# ahrs.net
KiCad netlist of a schematic drawn in EAGLE
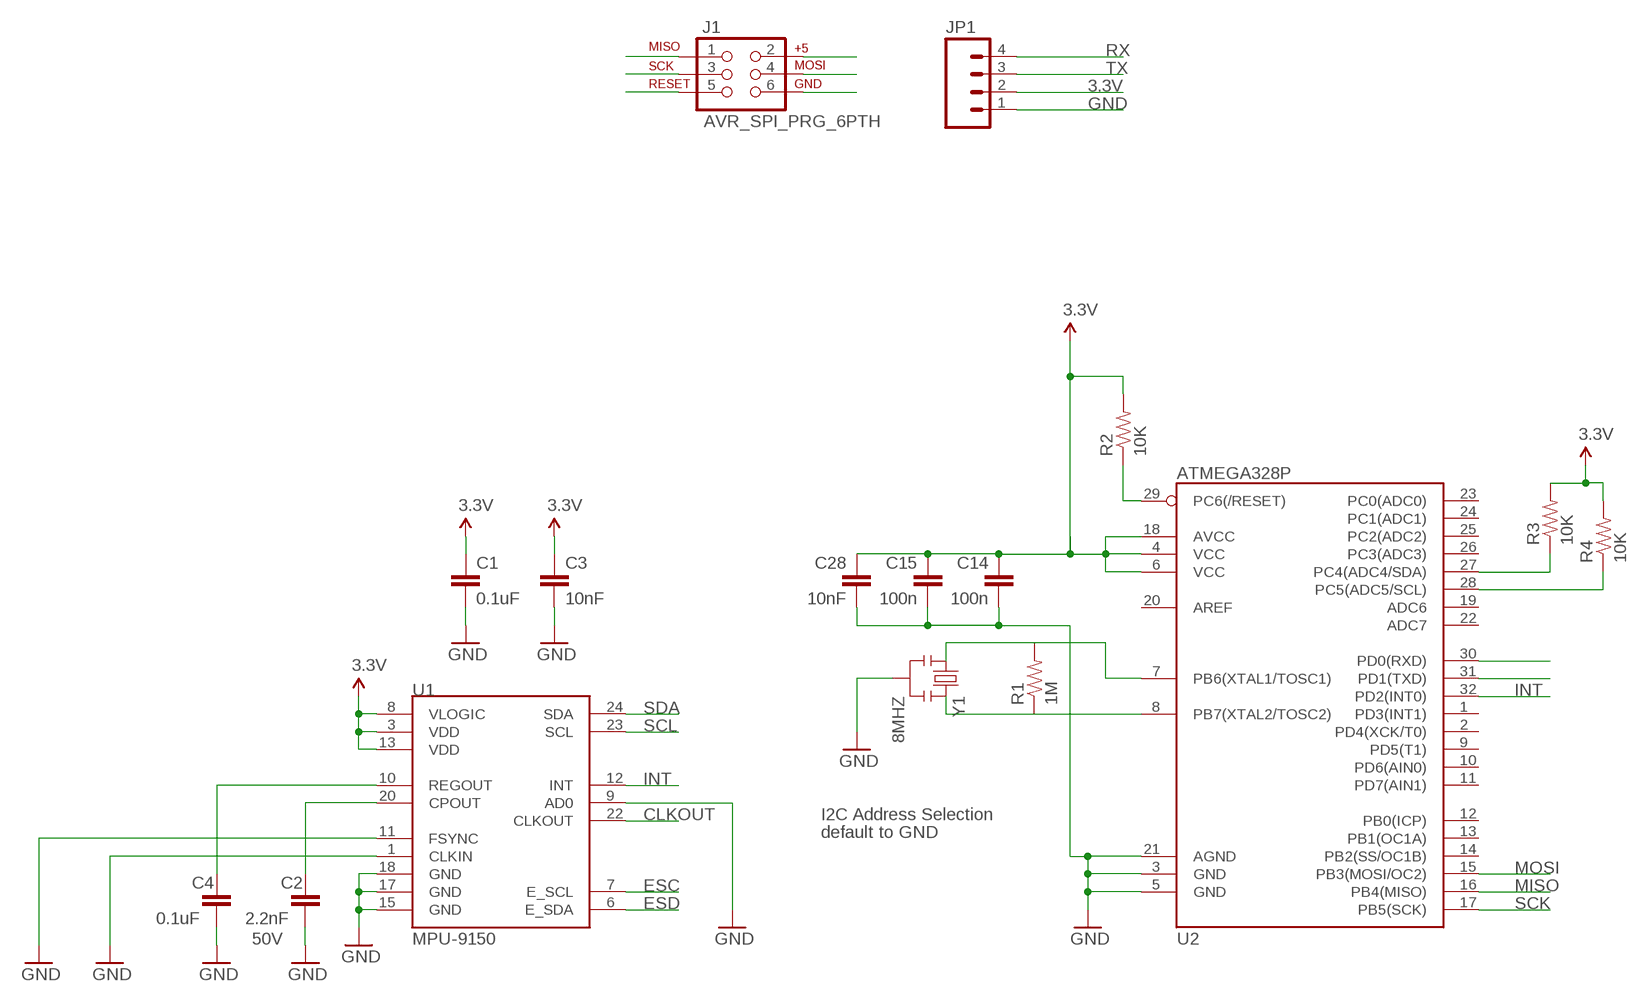
[diagram p0: schematic, sheet 1]

(export (version "E")
  (design (tool "Eeschema 10.0.6"))
  (components
    (comp (ref "C1")
      (value "0.1uF")
      (footprint "eagle-import:0603-CAP")
      (libsource (lib "eagle-import") (part "CAP0603-CAP"))
    )
    (comp (ref "C2")
      (value "2.2nF")
      (footprint "eagle-import:0603-CAP")
      (libsource (lib "eagle-import") (part "CAP0603-CAP"))
    )
    (comp (ref "C3")
      (value "10nF")
      (footprint "eagle-import:0603-CAP")
      (libsource (lib "eagle-import") (part "CAP0603-CAP"))
    )
    (comp (ref "C4")
      (value "0.1uF")
      (footprint "eagle-import:0603-CAP")
      (libsource (lib "eagle-import") (part "CAP0603-CAP"))
    )
    (comp (ref "C14")
      (value "100n")
      (footprint "eagle-import:C0603-ROUND")
      (libsource (lib "eagle-import") (part "C-EU0603-RND"))
    )
    (comp (ref "C15")
      (value "100n")
      (footprint "eagle-import:C0603-ROUND")
      (libsource (lib "eagle-import") (part "C-EU0603-RND"))
    )
    (comp (ref "C28")
      (value "10nF")
      (footprint "eagle-import:0603-CAP")
      (libsource (lib "eagle-import") (part "CAP0603-CAP"))
    )
    (comp (ref "J1")
      (value "AVR_SPI_PRG_6PTH")
      (footprint "eagle-import:2X3")
      (libsource (lib "eagle-import") (part "AVR_SPI_PRG_6PTH"))
    )
    (comp (ref "JP1")
      (value "M04PTH")
      (footprint "eagle-import:1X04")
      (libsource (lib "eagle-import") (part "M04PTH"))
    )
    (comp (ref "R1")
      (value "1M")
      (footprint "eagle-import:0603-RES")
      (libsource (lib "eagle-import") (part "RESISTOR0603-RES"))
    )
    (comp (ref "R2")
      (value "10K")
      (footprint "eagle-import:0603-RES")
      (libsource (lib "eagle-import") (part "RESISTOR0603-RES"))
    )
    (comp (ref "R3")
      (value "10K")
      (footprint "eagle-import:0603-RES")
      (libsource (lib "eagle-import") (part "RESISTOR0603-RES"))
    )
    (comp (ref "R4")
      (value "10K")
      (footprint "eagle-import:0603-RES")
      (libsource (lib "eagle-import") (part "RESISTOR0603-RES"))
    )
    (comp (ref "U1")
      (value "MPU-9150")
      (footprint "eagle-import:QFN-24-NP")
      (libsource (lib "eagle-import") (part "MPU-9150QFN-24-NP"))
    )
    (comp (ref "U2")
      (value "ATMEGA328P")
      (footprint "eagle-import:TQFP32-08")
      (libsource (lib "eagle-import") (part "ATMEGA328_SMT"))
    )
    (comp (ref "Y1")
      (value "8MHZ")
      (footprint "eagle-import:RESONATOR-SMD")
      (libsource (lib "eagle-import") (part "RESONATOR8MHZ"))
    )
  )
  (nets
    (net (code "1") (name "/CLKOUT") (class "Default")
      (node (ref "U1") (pin "22") (pinfunction "CLKOUT_22") (pintype "bidirectional"))
    )
    (net (code "2") (name "/ESC") (class "Default")
      (node (ref "U1") (pin "7") (pinfunction "E_SCL_7") (pintype "bidirectional"))
    )
    (net (code "3") (name "/ESD") (class "Default")
      (node (ref "U1") (pin "6") (pinfunction "E_SDA_6") (pintype "bidirectional"))
    )
    (net (code "4") (name "/INT") (class "Default")
      (node (ref "U1") (pin "12") (pinfunction "INT_12") (pintype "bidirectional"))
      (node (ref "U2") (pin "32") (pinfunction "PD2(INT0)_32") (pintype "bidirectional"))
    )
    (net (code "5") (name "/MISO") (class "Default")
      (node (ref "J1") (pin "1") (pinfunction "1_1") (pintype "passive"))
      (node (ref "U2") (pin "16") (pinfunction "PB4(MISO)_16") (pintype "bidirectional"))
    )
    (net (code "6") (name "/MOSI") (class "Default")
      (node (ref "J1") (pin "4") (pinfunction "4_4") (pintype "passive"))
      (node (ref "U2") (pin "15") (pinfunction "PB3(MOSI/OC2)_15") (pintype "bidirectional"))
    )
    (net (code "7") (name "/RESET") (class "Default")
      (node (ref "J1") (pin "5") (pinfunction "5_5") (pintype "passive"))
      (node (ref "R2") (pin "1") (pinfunction "1_1") (pintype "passive"))
      (node (ref "U2") (pin "29") (pinfunction "PC6(/RESET)_29") (pintype "bidirectional"))
    )
    (net (code "8") (name "/RX") (class "Default")
      (node (ref "JP1") (pin "4") (pinfunction "4_4") (pintype "passive"))
      (node (ref "U2") (pin "30") (pinfunction "PD0(RXD)_30") (pintype "bidirectional"))
    )
    (net (code "9") (name "/SCK") (class "Default")
      (node (ref "J1") (pin "3") (pinfunction "3_3") (pintype "passive"))
      (node (ref "U2") (pin "17") (pinfunction "PB5(SCK)_17") (pintype "bidirectional"))
    )
    (net (code "10") (name "/SCL") (class "Default")
      (node (ref "R4") (pin "1") (pinfunction "1_1") (pintype "passive"))
      (node (ref "U1") (pin "23") (pinfunction "SCL_23") (pintype "bidirectional"))
      (node (ref "U2") (pin "28") (pinfunction "PC5(ADC5/SCL)_28") (pintype "bidirectional"))
    )
    (net (code "11") (name "/SDA") (class "Default")
      (node (ref "R3") (pin "1") (pinfunction "1_1") (pintype "passive"))
      (node (ref "U1") (pin "24") (pinfunction "SDA_24") (pintype "bidirectional"))
      (node (ref "U2") (pin "27") (pinfunction "PC4(ADC4/SDA)_27") (pintype "bidirectional"))
    )
    (net (code "12") (name "/TX") (class "Default")
      (node (ref "JP1") (pin "3") (pinfunction "3_3") (pintype "passive"))
      (node (ref "U2") (pin "31") (pinfunction "PD1(TXD)_31") (pintype "bidirectional"))
    )
    (net (code "13") (name "3.3V") (class "Default")
      (node (ref "C1") (pin "1") (pinfunction "1_1") (pintype "passive"))
      (node (ref "C14") (pin "1") (pinfunction "1_1") (pintype "passive"))
      (node (ref "C15") (pin "1") (pinfunction "1_1") (pintype "passive"))
      (node (ref "C28") (pin "1") (pinfunction "1_1") (pintype "passive"))
      (node (ref "C3") (pin "1") (pinfunction "1_1") (pintype "passive"))
      (node (ref "J1") (pin "2") (pinfunction "2_2") (pintype "passive"))
      (node (ref "JP1") (pin "2") (pinfunction "2_2") (pintype "passive"))
      (node (ref "R2") (pin "2") (pinfunction "2_2") (pintype "passive"))
      (node (ref "R3") (pin "2") (pinfunction "2_2") (pintype "passive"))
      (node (ref "R4") (pin "2") (pinfunction "2_2") (pintype "passive"))
      (node (ref "U1") (pin "13") (pinfunction "VDD_13") (pintype "bidirectional"))
      (node (ref "U1") (pin "3") (pinfunction "VDD_3") (pintype "bidirectional"))
      (node (ref "U1") (pin "8") (pinfunction "VLOGIC_8") (pintype "bidirectional"))
      (node (ref "U2") (pin "18") (pinfunction "AVCC_18") (pintype "bidirectional"))
      (node (ref "U2") (pin "4") (pinfunction "VCC_4") (pintype "bidirectional"))
      (node (ref "U2") (pin "6") (pinfunction "VCC_6") (pintype "bidirectional"))
    )
    (net (code "14") (name "GND") (class "Default")
      (node (ref "C1") (pin "2") (pinfunction "2_2") (pintype "passive"))
      (node (ref "C14") (pin "2") (pinfunction "2_2") (pintype "passive"))
      (node (ref "C15") (pin "2") (pinfunction "2_2") (pintype "passive"))
      (node (ref "C2") (pin "2") (pinfunction "2_2") (pintype "passive"))
      (node (ref "C28") (pin "2") (pinfunction "2_2") (pintype "passive"))
      (node (ref "C3") (pin "2") (pinfunction "2_2") (pintype "passive"))
      (node (ref "C4") (pin "2") (pinfunction "2_2") (pintype "passive"))
      (node (ref "J1") (pin "6") (pinfunction "6_6") (pintype "passive"))
      (node (ref "JP1") (pin "1") (pinfunction "1_1") (pintype "passive"))
      (node (ref "U1") (pin "1") (pinfunction "CLKIN_1") (pintype "bidirectional"))
      (node (ref "U1") (pin "11") (pinfunction "FSYNC_11") (pintype "bidirectional"))
      (node (ref "U1") (pin "15") (pinfunction "GND_15") (pintype "bidirectional"))
      (node (ref "U1") (pin "17") (pinfunction "GND_17") (pintype "bidirectional"))
      (node (ref "U1") (pin "18") (pinfunction "GND_18") (pintype "bidirectional"))
      (node (ref "U1") (pin "9") (pinfunction "AD0_9") (pintype "bidirectional"))
      (node (ref "U2") (pin "21") (pinfunction "AGND_21") (pintype "bidirectional"))
      (node (ref "U2") (pin "3") (pinfunction "GND_3") (pintype "bidirectional"))
      (node (ref "U2") (pin "5") (pinfunction "GND_5") (pintype "bidirectional"))
      (node (ref "Y1") (pin "2") (pinfunction "2_2") (pintype "passive"))
    )
    (net (code "15") (name "Net-(U1-CPOUT)") (class "Default")
      (node (ref "C2") (pin "1") (pinfunction "1_1") (pintype "passive"))
      (node (ref "U1") (pin "20") (pinfunction "CPOUT_20") (pintype "bidirectional"))
    )
    (net (code "16") (name "Net-(U1-REGOUT)") (class "Default")
      (node (ref "C4") (pin "1") (pinfunction "1_1") (pintype "passive"))
      (node (ref "U1") (pin "10") (pinfunction "REGOUT_10") (pintype "bidirectional"))
    )
    (net (code "17") (name "Net-(U2-PB6(XTAL1{slash}TOSC1))") (class "Default")
      (node (ref "R1") (pin "2") (pinfunction "2_2") (pintype "passive"))
      (node (ref "U2") (pin "7") (pinfunction "PB6(XTAL1/TOSC1)_7") (pintype "bidirectional"))
      (node (ref "Y1") (pin "1") (pinfunction "1_1") (pintype "passive"))
    )
    (net (code "18") (name "Net-(U2-PB7(XTAL2{slash}TOSC2))") (class "Default")
      (node (ref "R1") (pin "1") (pinfunction "1_1") (pintype "passive"))
      (node (ref "U2") (pin "8") (pinfunction "PB7(XTAL2/TOSC2)_8") (pintype "bidirectional"))
      (node (ref "Y1") (pin "3") (pinfunction "3_3") (pintype "passive"))
    )
    (net (code "19") (name "unconnected-(U2-ADC6-Pad19)") (class "Default")
      (node (ref "U2") (pin "19") (pinfunction "ADC6_19") (pintype "bidirectional"))
    )
    (net (code "20") (name "unconnected-(U2-ADC7-Pad22)") (class "Default")
      (node (ref "U2") (pin "22") (pinfunction "ADC7_22") (pintype "bidirectional"))
    )
    (net (code "21") (name "unconnected-(U2-AREF-Pad20)") (class "Default")
      (node (ref "U2") (pin "20") (pinfunction "AREF_20") (pintype "bidirectional"))
    )
    (net (code "22") (name "unconnected-(U2-PB0(ICP)-Pad12)") (class "Default")
      (node (ref "U2") (pin "12") (pinfunction "PB0(ICP)_12") (pintype "bidirectional"))
    )
    (net (code "23") (name "unconnected-(U2-PB1(OC1A)-Pad13)") (class "Default")
      (node (ref "U2") (pin "13") (pinfunction "PB1(OC1A)_13") (pintype "bidirectional"))
    )
    (net (code "24") (name "unconnected-(U2-PB2(SS{slash}OC1B)-Pad14)") (class "Default")
      (node (ref "U2") (pin "14") (pinfunction "PB2(SS/OC1B)_14") (pintype "bidirectional"))
    )
    (net (code "25") (name "unconnected-(U2-PC0(ADC0)-Pad23)") (class "Default")
      (node (ref "U2") (pin "23") (pinfunction "PC0(ADC0)_23") (pintype "bidirectional"))
    )
    (net (code "26") (name "unconnected-(U2-PC1(ADC1)-Pad24)") (class "Default")
      (node (ref "U2") (pin "24") (pinfunction "PC1(ADC1)_24") (pintype "bidirectional"))
    )
    (net (code "27") (name "unconnected-(U2-PC2(ADC2)-Pad25)") (class "Default")
      (node (ref "U2") (pin "25") (pinfunction "PC2(ADC2)_25") (pintype "bidirectional"))
    )
    (net (code "28") (name "unconnected-(U2-PC3(ADC3)-Pad26)") (class "Default")
      (node (ref "U2") (pin "26") (pinfunction "PC3(ADC3)_26") (pintype "bidirectional"))
    )
    (net (code "29") (name "unconnected-(U2-PD3(INT1)-Pad1)") (class "Default")
      (node (ref "U2") (pin "1") (pinfunction "PD3(INT1)_1") (pintype "bidirectional"))
    )
    (net (code "30") (name "unconnected-(U2-PD4(XCK{slash}T0)-Pad2)") (class "Default")
      (node (ref "U2") (pin "2") (pinfunction "PD4(XCK/T0)_2") (pintype "bidirectional"))
    )
    (net (code "31") (name "unconnected-(U2-PD5(T1)-Pad9)") (class "Default")
      (node (ref "U2") (pin "9") (pinfunction "PD5(T1)_9") (pintype "bidirectional"))
    )
    (net (code "32") (name "unconnected-(U2-PD6(AIN0)-Pad10)") (class "Default")
      (node (ref "U2") (pin "10") (pinfunction "PD6(AIN0)_10") (pintype "bidirectional"))
    )
    (net (code "33") (name "unconnected-(U2-PD7(AIN1)-Pad11)") (class "Default")
      (node (ref "U2") (pin "11") (pinfunction "PD7(AIN1)_11") (pintype "bidirectional"))
    )
  )
)
